# power_managment.net
KiCad netlist of a schematic drawn in Altium Designer
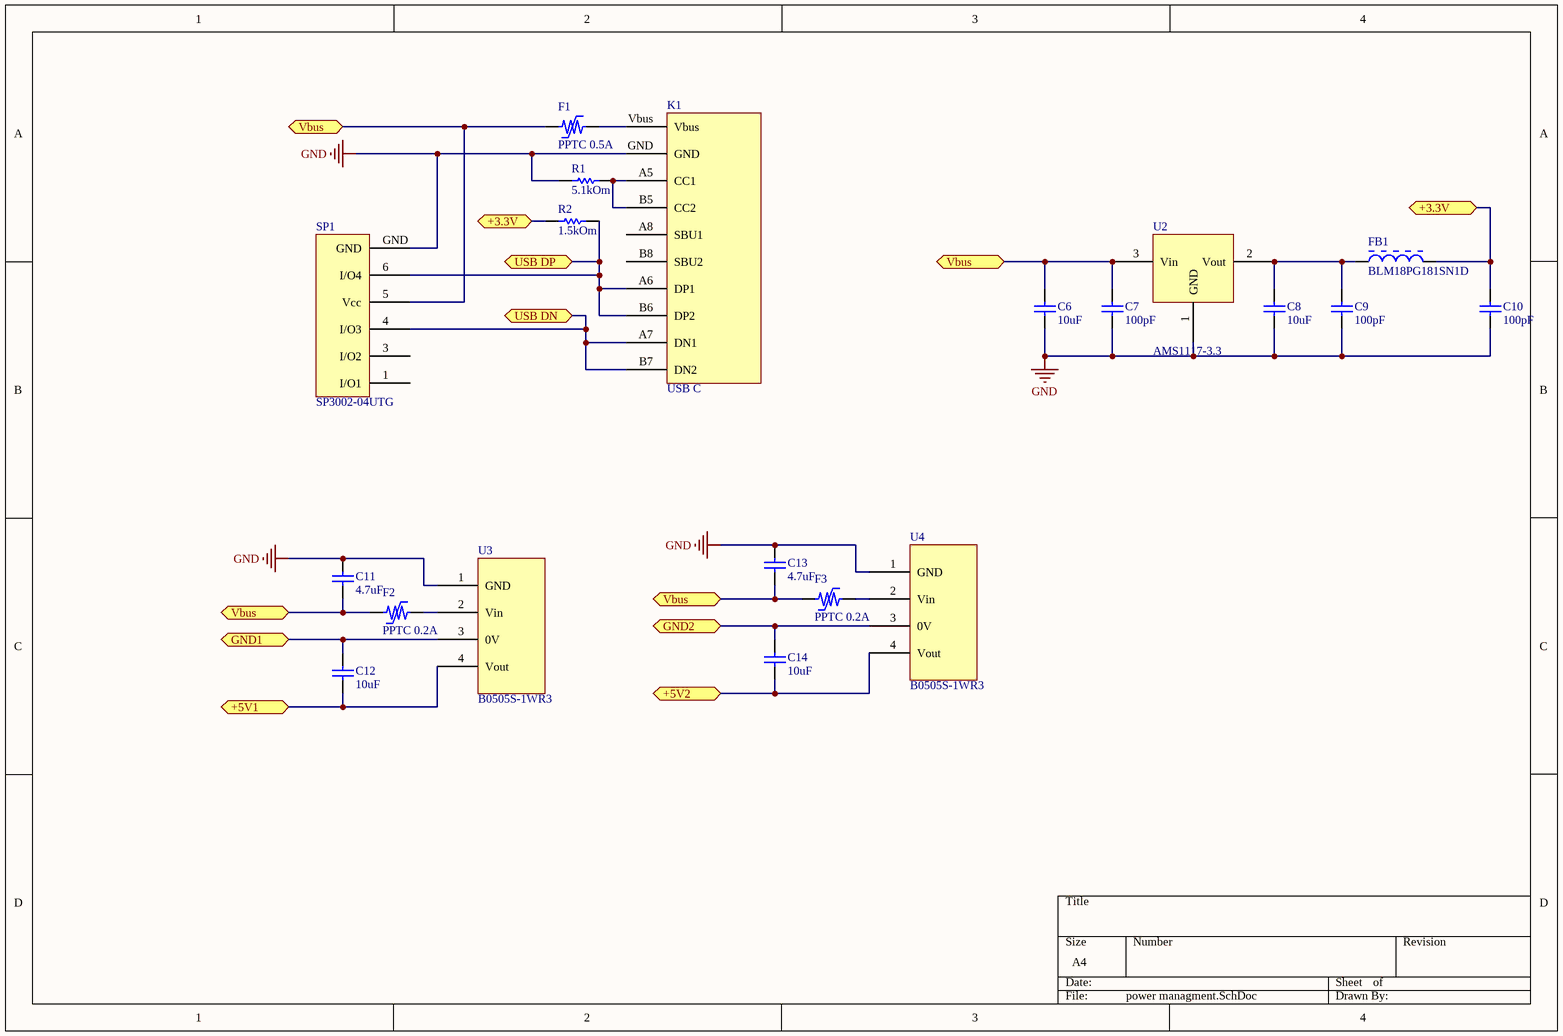
[diagram p0: power managment.SchDoc]

(export (version "E")
  (design (tool "Eeschema 10.0.6"))
  (components
    (comp (ref "C6")
      (value "10uF")
      (footprint "CAPC1608X90X35ML10T15")
      (fields (field (name "MANUFACTURER") "Murata") (field (name "PART NUMBER") "GCM1885C2A101JA16D"))
      (libsource (lib "Altium Content Vault") (part "CAP"))
    )
    (comp (ref "C7")
      (value "100pF")
      (footprint "CAPC1608X90X35ML10T15")
      (fields (field (name "MANUFACTURER") "Murata") (field (name "PART NUMBER") "GCM1885C2A101JA16D"))
      (libsource (lib "Altium Content Vault") (part "CAP"))
    )
    (comp (ref "C8")
      (value "10uF")
      (footprint "CAPC1608X90X35ML10T15")
      (fields (field (name "MANUFACTURER") "Murata") (field (name "PART NUMBER") "GCM1885C2A101JA16D"))
      (libsource (lib "Altium Content Vault") (part "CAP"))
    )
    (comp (ref "C9")
      (value "100pF")
      (footprint "CAPC1608X90X35ML10T15")
      (fields (field (name "MANUFACTURER") "Murata") (field (name "PART NUMBER") "GCM1885C2A101JA16D"))
      (libsource (lib "Altium Content Vault") (part "CAP"))
    )
    (comp (ref "C10")
      (value "100pF")
      (footprint "CAPC1608X90X35ML10T15")
      (fields (field (name "MANUFACTURER") "Murata") (field (name "PART NUMBER") "GCM1885C2A101JA16D"))
      (libsource (lib "Altium Content Vault") (part "CAP"))
    )
    (comp (ref "C11")
      (value "4.7uF")
      (footprint "CAPC1608X90X35ML10T15")
      (fields (field (name "MANUFACTURER") "Murata") (field (name "PART NUMBER") "GCM1885C2A101JA16D"))
      (libsource (lib "Altium Content Vault") (part "CAP"))
    )
    (comp (ref "C12")
      (value "10uF")
      (footprint "CAPC1608X90X35ML10T15")
      (fields (field (name "MANUFACTURER") "Murata") (field (name "PART NUMBER") "GCM1885C2A101JA16D"))
      (libsource (lib "Altium Content Vault") (part "CAP"))
    )
    (comp (ref "C13")
      (value "4.7uF")
      (footprint "CAPC1608X90X35ML10T15")
      (fields (field (name "MANUFACTURER") "Murata") (field (name "PART NUMBER") "GCM1885C2A101JA16D"))
      (libsource (lib "Altium Content Vault") (part "CAP"))
    )
    (comp (ref "C14")
      (value "10uF")
      (footprint "CAPC1608X90X35ML10T15")
      (fields (field (name "MANUFACTURER") "Murata") (field (name "PART NUMBER") "GCM1885C2A101JA16D"))
      (libsource (lib "Altium Content Vault") (part "CAP"))
    )
    (comp (ref "F1")
      (value "PPTC 0.5A")
      (footprint "PTC 0603")
      (libsource (lib "lib") (part "PTC Resettable Fuse"))
    )
    (comp (ref "F2")
      (value "PPTC 0.2A")
      (footprint "PTC 0603")
      (libsource (lib "lib") (part "PTC Resettable Fuse"))
    )
    (comp (ref "F3")
      (value "PPTC 0.2A")
      (footprint "PTC 0603")
      (libsource (lib "lib") (part "PTC Resettable Fuse"))
    )
    (comp (ref "FB1")
      (value "BLM18PG181SN1D")
      (footprint "MURA-BLM18PG_KG-CHIP-2_V2")
      (fields (field (name "MANUFACTURER") "Murata"))
      (libsource (lib "Altium Content Vault") (part "MURA-FB-2"))
    )
    (comp (ref "K1") (value "USB C") (footprint "USB type C") (libsource (lib "lib") (part "USB C")))
    (comp (ref "R1")
      (value "5.1kOm")
      (footprint "RESC1608X55X30ML20T10")
      (fields (field (name "PART NUMBER") "RK73H1JTTD5101F") (field (name "MANUFACTURER") "KOA Speer"))
      (libsource (lib "Altium Content Vault") (part "RES"))
    )
    (comp (ref "R2")
      (value "1.5kOm")
      (footprint "RESC1608X55X30ML20T10")
      (fields (field (name "PART NUMBER") "RK73H1JTTD5101F") (field (name "MANUFACTURER") "KOA Speer"))
      (libsource (lib "Altium Content Vault") (part "RES"))
    )
    (comp (ref "SP1")
      (value "SP3002-04UTG")
      (footprint "uDFN-6")
      (libsource (lib "lib") (part "SP3002-04UTG"))
    )
    (comp (ref "U2") (value "AMS1117-3.3") (footprint "AMS1117") (libsource (lib "lib") (part "AMS1117-3.3")))
    (comp (ref "U3")
      (value "B0505S-1WR3")
      (footprint "Dip4 package")
      (libsource (lib "lib") (part "B0505S-1WR3"))
    )
    (comp (ref "U4")
      (value "B0505S-1WR3")
      (footprint "Dip4 package")
      (libsource (lib "lib") (part "B0505S-1WR3"))
    )
  )
  (nets
    (net (code "1") (name "/+3.3V") (class "Default")
      (node (ref "C10") (pin "2") (pinfunction "2_2") (pintype "passive"))
      (node (ref "FB1") (pin "2") (pinfunction "2_2") (pintype "passive"))
      (node (ref "R2") (pin "1") (pinfunction "1_1") (pintype "passive"))
    )
    (net (code "2") (name "/+5V1") (class "Default")
      (node (ref "C12") (pin "1") (pinfunction "1_1") (pintype "passive"))
      (node (ref "U3") (pin "4") (pinfunction "Vout_4") (pintype "passive"))
    )
    (net (code "3") (name "/+5V2") (class "Default")
      (node (ref "C14") (pin "1") (pinfunction "1_1") (pintype "passive"))
      (node (ref "U4") (pin "4") (pinfunction "Vout_4") (pintype "passive"))
    )
    (net (code "4") (name "/GND1") (class "Default")
      (node (ref "C12") (pin "2") (pinfunction "2_2") (pintype "passive"))
      (node (ref "U3") (pin "3") (pinfunction "0V_3") (pintype "passive"))
    )
    (net (code "5") (name "/GND2") (class "Default")
      (node (ref "C14") (pin "2") (pinfunction "2_2") (pintype "passive"))
      (node (ref "U4") (pin "3") (pinfunction "0V_3") (pintype "passive"))
    )
    (net (code "6") (name "/USB DN") (class "Default")
      (node (ref "K1") (pin "A7") (pinfunction "DN1_A7") (pintype "passive"))
      (node (ref "K1") (pin "B7") (pinfunction "DN2_B7") (pintype "passive"))
      (node (ref "SP1") (pin "4") (pinfunction "I/O3_4") (pintype "passive"))
    )
    (net (code "7") (name "/USB DP") (class "Default")
      (node (ref "K1") (pin "A6") (pinfunction "DP1_A6") (pintype "passive"))
      (node (ref "K1") (pin "B6") (pinfunction "DP2_B6") (pintype "passive"))
      (node (ref "R2") (pin "2") (pinfunction "2_2") (pintype "passive"))
      (node (ref "SP1") (pin "6") (pinfunction "I/O4_6") (pintype "passive"))
    )
    (net (code "8") (name "/Vbus") (class "Default")
      (node (ref "C11") (pin "1") (pinfunction "1_1") (pintype "passive"))
      (node (ref "C13") (pin "1") (pinfunction "1_1") (pintype "passive"))
      (node (ref "C6") (pin "2") (pinfunction "2_2") (pintype "passive"))
      (node (ref "C7") (pin "2") (pinfunction "2_2") (pintype "passive"))
      (node (ref "F1") (pin "1") (pinfunction "1_1") (pintype "passive"))
      (node (ref "F2") (pin "1") (pinfunction "1_1") (pintype "passive"))
      (node (ref "F3") (pin "1") (pinfunction "1_1") (pintype "passive"))
      (node (ref "SP1") (pin "5") (pinfunction "Vcc_5") (pintype "passive"))
      (node (ref "U2") (pin "3") (pinfunction "Vin_3") (pintype "passive"))
    )
    (net (code "9") (name "GND") (class "Default")
      (node (ref "C10") (pin "1") (pinfunction "1_1") (pintype "passive"))
      (node (ref "C11") (pin "2") (pinfunction "2_2") (pintype "passive"))
      (node (ref "C13") (pin "2") (pinfunction "2_2") (pintype "passive"))
      (node (ref "C6") (pin "1") (pinfunction "1_1") (pintype "passive"))
      (node (ref "C7") (pin "1") (pinfunction "1_1") (pintype "passive"))
      (node (ref "C8") (pin "1") (pinfunction "1_1") (pintype "passive"))
      (node (ref "C9") (pin "1") (pinfunction "1_1") (pintype "passive"))
      (node (ref "K1") (pin "GND") (pinfunction "GND_GND") (pintype "passive"))
      (node (ref "R1") (pin "1") (pinfunction "1_1") (pintype "passive"))
      (node (ref "SP1") (pin "GND") (pinfunction "GND_GND") (pintype "passive"))
      (node (ref "U2") (pin "1") (pinfunction "GND_1") (pintype "passive"))
      (node (ref "U3") (pin "1") (pinfunction "GND_1") (pintype "passive"))
      (node (ref "U4") (pin "1") (pinfunction "GND_1") (pintype "passive"))
    )
    (net (code "10") (name "Net-(F1-Pad2)") (class "Default")
      (node (ref "F1") (pin "2") (pinfunction "2_2") (pintype "passive"))
      (node (ref "K1") (pin "Vbus") (pinfunction "Vbus_Vbus") (pintype "passive"))
    )
    (net (code "11") (name "Net-(K1-CC1)") (class "Default")
      (node (ref "K1") (pin "A5") (pinfunction "CC1_A5") (pintype "passive"))
      (node (ref "K1") (pin "B5") (pinfunction "CC2_B5") (pintype "passive"))
      (node (ref "R1") (pin "2") (pinfunction "2_2") (pintype "passive"))
    )
    (net (code "12") (name "Net-(U2-Vout)") (class "Default")
      (node (ref "C8") (pin "2") (pinfunction "2_2") (pintype "passive"))
      (node (ref "C9") (pin "2") (pinfunction "2_2") (pintype "passive"))
      (node (ref "FB1") (pin "1") (pinfunction "1_1") (pintype "passive"))
      (node (ref "U2") (pin "2") (pinfunction "Vout_2") (pintype "passive"))
    )
    (net (code "13") (name "Net-(U3-Vin)") (class "Default")
      (node (ref "F2") (pin "2") (pinfunction "2_2") (pintype "passive"))
      (node (ref "U3") (pin "2") (pinfunction "Vin_2") (pintype "passive"))
    )
    (net (code "14") (name "Net-(U4-Vin)") (class "Default")
      (node (ref "F3") (pin "2") (pinfunction "2_2") (pintype "passive"))
      (node (ref "U4") (pin "2") (pinfunction "Vin_2") (pintype "passive"))
    )
    (net (code "15") (name "unconnected-(K1-SBU1-PadA8)") (class "Default")
      (node (ref "K1") (pin "A8") (pinfunction "SBU1_A8") (pintype "passive"))
    )
    (net (code "16") (name "unconnected-(K1-SBU2-PadB8)") (class "Default")
      (node (ref "K1") (pin "B8") (pinfunction "SBU2_B8") (pintype "passive"))
    )
    (net (code "17") (name "unconnected-(SP1-I{slash}O1-Pad1)") (class "Default")
      (node (ref "SP1") (pin "1") (pinfunction "I/O1_1") (pintype "passive"))
    )
    (net (code "18") (name "unconnected-(SP1-I{slash}O2-Pad3)") (class "Default")
      (node (ref "SP1") (pin "3") (pinfunction "I/O2_3") (pintype "passive"))
    )
  )
)
